# RFID.net
KiCad netlist of a schematic drawn in Altium Designer
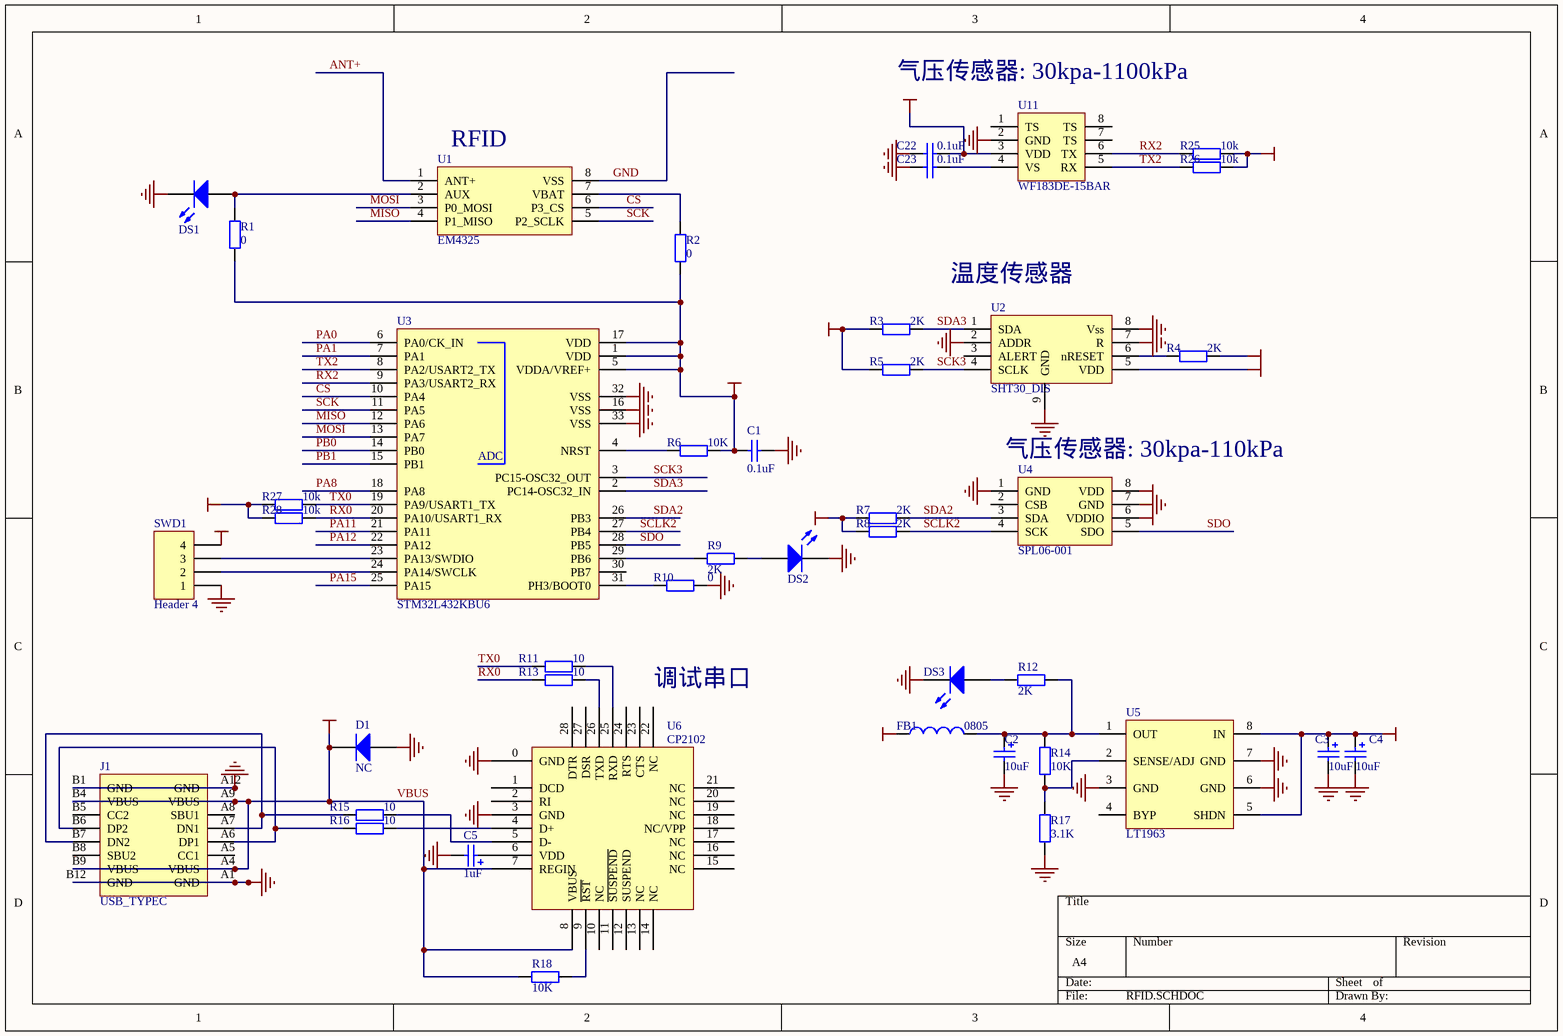
[diagram p0: RFID.SCHDOC]

(export (version "E")
  (design (tool "Eeschema 10.0.6"))
  (components
    (comp (ref "C1")
      (value "0.1uF")
      (footprint "0805")
      (description "Capacitor")
      (fields (field (name "PUBLISHER") "Altium Limited"))
      (libsource (lib "SCHALL") (part "Cap"))
    )
    (comp (ref "C2")
      (value "10uF")
      (footprint "1206")
      (description "Polarized Capacitor (Radial)")
      (fields (field (name "PUBLISHER") "Altium Limited"))
      (libsource (lib "SCHALL") (part "Cap Pol1"))
    )
    (comp (ref "C3")
      (value "10uF")
      (footprint "1206")
      (description "Polarized Capacitor (Radial)")
      (fields (field (name "PUBLISHER") "Altium Limited"))
      (libsource (lib "SCHALL") (part "Cap Pol1"))
    )
    (comp (ref "C4")
      (value "10uF")
      (footprint "1206")
      (description "Polarized Capacitor (Radial)")
      (fields (field (name "PUBLISHER") "Altium Limited"))
      (libsource (lib "SCHALL") (part "Cap Pol1"))
    )
    (comp (ref "C5")
      (value "1uF")
      (footprint "0805")
      (description "Polarized Capacitor (Radial)")
      (fields (field (name "PUBLISHER") "Altium Limited"))
      (libsource (lib "SCHALL") (part "Cap Pol1"))
    )
    (comp (ref "C22")
      (value "0.1uF")
      (footprint "0805")
      (description "Capacitor")
      (fields (field (name "PUBLISHER") "Altium Limited"))
      (libsource (lib "SCHALL") (part "Cap"))
    )
    (comp (ref "C23")
      (value "0.1uF")
      (footprint "0805")
      (description "Capacitor")
      (fields (field (name "PUBLISHER") "Altium Limited"))
      (libsource (lib "SCHALL") (part "Cap"))
    )
    (comp (ref "D1")
      (value "NC")
      (footprint "DFLS240L")
      (description "Default Diode")
      (fields (field (name "PUBLISHER") "Altium Limited"))
      (libsource (lib "SCHALL") (part "Diode"))
    )
    (comp (ref "DS1")
      (value "LED")
      (footprint "0603")
      (description "Typical BLUE SiC LED")
      (fields (field (name "PUBLISHER") "Altium Limited"))
      (libsource (lib "sch_lib") (part "LED"))
    )
    (comp (ref "DS2")
      (value "LED")
      (footprint "0603")
      (description "Typical BLUE SiC LED")
      (fields (field (name "PUBLISHER") "Altium Limited"))
      (libsource (lib "SCHALL") (part "LED"))
    )
    (comp (ref "DS3")
      (value "LED")
      (footprint "0603")
      (description "Typical BLUE SiC LED")
      (fields (field (name "PUBLISHER") "Altium Limited"))
      (libsource (lib "SCHALL") (part "LED"))
    )
    (comp (ref "FB1")
      (value "0805")
      (footprint "0805")
      (description "Inductor")
      (fields (field (name "PUBLISHER") "Altium Limited"))
      (libsource (lib "SCHALL") (part "Inductor"))
    )
    (comp (ref "J1")
      (value "USB_TYPEC")
      (footprint "USB_TYPEC_16")
      (libsource (lib "sch_lib") (part "USB_TYPEC"))
    )
    (comp (ref "R1")
      (value "0")
      (footprint "0603")
      (description "Resistor")
      (fields (field (name "PUBLISHER") "Altium Limited"))
      (libsource (lib "") (part "Res2_2"))
    )
    (comp (ref "R2")
      (value "0")
      (footprint "0603")
      (description "Resistor")
      (fields (field (name "PUBLISHER") "Altium Limited"))
      (libsource (lib "") (part "Res2_2"))
    )
    (comp (ref "R3")
      (value "2K")
      (footprint "0603")
      (description "Resistor")
      (fields (field (name "PUBLISHER") "Altium Limited"))
      (libsource (lib "SCHALL") (part "Res2"))
    )
    (comp (ref "R4")
      (value "2K")
      (footprint "0603")
      (description "Resistor")
      (fields (field (name "PUBLISHER") "Altium Limited"))
      (libsource (lib "SCHALL") (part "Res2"))
    )
    (comp (ref "R5")
      (value "2K")
      (footprint "0603")
      (description "Resistor")
      (fields (field (name "PUBLISHER") "Altium Limited"))
      (libsource (lib "SCHALL") (part "Res2"))
    )
    (comp (ref "R6")
      (value "10K")
      (footprint "0603")
      (description "Resistor")
      (fields (field (name "PUBLISHER") "Altium Limited"))
      (libsource (lib "") (part "Res2_1"))
    )
    (comp (ref "R7")
      (value "2K")
      (footprint "0603")
      (description "Resistor")
      (fields (field (name "PUBLISHER") "Altium Limited"))
      (libsource (lib "SCHALL") (part "Res2"))
    )
    (comp (ref "R8")
      (value "2K")
      (footprint "0603")
      (description "Resistor")
      (fields (field (name "PUBLISHER") "Altium Limited"))
      (libsource (lib "SCHALL") (part "Res2"))
    )
    (comp (ref "R9")
      (value "2K")
      (footprint "0603")
      (description "Resistor")
      (fields (field (name "PUBLISHER") "Altium Limited"))
      (libsource (lib "") (part "Res2_1"))
    )
    (comp (ref "R10")
      (value "0")
      (footprint "0603")
      (description "Resistor")
      (fields (field (name "PUBLISHER") "Altium Limited"))
      (libsource (lib "") (part "Res2_1"))
    )
    (comp (ref "R11")
      (value "10")
      (footprint "0603")
      (description "Resistor")
      (fields (field (name "PUBLISHER") "Altium Limited"))
      (libsource (lib "SCHALL") (part "Res2"))
    )
    (comp (ref "R12")
      (value "2K")
      (footprint "0603")
      (description "Resistor")
      (fields (field (name "PUBLISHER") "Altium Limited"))
      (libsource (lib "SCHALL") (part "Res2"))
    )
    (comp (ref "R13")
      (value "10")
      (footprint "0603")
      (description "Resistor")
      (fields (field (name "PUBLISHER") "Altium Limited"))
      (libsource (lib "SCHALL") (part "Res2"))
    )
    (comp (ref "R14")
      (value "10K")
      (footprint "0603")
      (description "Resistor")
      (fields (field (name "PUBLISHER") "Altium Limited"))
      (libsource (lib "") (part "Res2_2"))
    )
    (comp (ref "R15")
      (value "10")
      (footprint "0603")
      (description "Resistor")
      (fields (field (name "PUBLISHER") "Altium Limited"))
      (libsource (lib "SCHALL") (part "Res2"))
    )
    (comp (ref "R16")
      (value "10")
      (footprint "0603")
      (description "Resistor")
      (fields (field (name "PUBLISHER") "Altium Limited"))
      (libsource (lib "SCHALL") (part "Res2"))
    )
    (comp (ref "R17")
      (value "3.1K")
      (footprint "0603")
      (description "Resistor")
      (fields (field (name "PUBLISHER") "Altium Limited"))
      (libsource (lib "") (part "Res2_2"))
    )
    (comp (ref "R18")
      (value "10K")
      (footprint "0603")
      (description "Resistor")
      (fields (field (name "PUBLISHER") "Altium Limited"))
      (libsource (lib "SCHALL") (part "Res"))
    )
    (comp (ref "R25")
      (value "10k")
      (footprint "0603")
      (description "Resistor")
      (fields (field (name "PUBLISHER") "Altium Limited"))
      (libsource (lib "SCHALL") (part "Res2"))
    )
    (comp (ref "R26")
      (value "10k")
      (footprint "0603")
      (description "Resistor")
      (fields (field (name "PUBLISHER") "Altium Limited"))
      (libsource (lib "SCHALL") (part "Res2"))
    )
    (comp (ref "R27")
      (value "10k")
      (footprint "0603")
      (description "Resistor")
      (fields (field (name "PUBLISHER") "Altium Limited"))
      (libsource (lib "SCHALL") (part "Res2"))
    )
    (comp (ref "R28")
      (value "10k")
      (footprint "0603")
      (description "Resistor")
      (fields (field (name "PUBLISHER") "Altium Limited"))
      (libsource (lib "SCHALL") (part "Res2"))
    )
    (comp (ref "SWD1")
      (value "Header 4")
      (footprint "HDR1X4")
      (description "Header, 4-Pin")
      (fields (field (name "PUBLISHER") "Altium Limited"))
      (libsource (lib "sch_lib") (part "Header 4"))
    )
    (comp (ref "U1") (value "EM4325") (footprint "EM4325") (libsource (lib "sch_lib") (part "EM4325")))
    (comp (ref "U2") (value "SHT30_DIS") (footprint "SHT30") (libsource (lib "sch_lib") (part "SHT30")))
    (comp (ref "U3")
      (value "STM32L432KBU6")
      (footprint "STM32L432KBU6")
      (libsource (lib "sch_lib") (part "STM32L432KBU6"))
    )
    (comp (ref "U4")
      (value "SPL06-001")
      (footprint "SPL06-001")
      (libsource (lib "sch_lib") (part "SPL06-001"))
    )
    (comp (ref "U5") (value "LT1963") (footprint "AT24C64") (libsource (lib "SCHALL") (part "LT1763")))
    (comp (ref "U6") (value "CP2102") (footprint "CP2102") (libsource (lib "SCHALL") (part "CP2102")))
    (comp (ref "U11")
      (value "WF183DE-15BAR")
      (footprint "WF183D")
      (libsource (lib "sch_lib") (part "WF183D"))
    )
  )
  (nets
    (net (code "1") (name "/ANT+") (class "Default")
      (node (ref "U1") (pin "1") (pinfunction "ANT+_1") (pintype "passive"))
    )
    (net (code "2") (name "/CS") (class "Default")
      (node (ref "U1") (pin "6") (pinfunction "P3_CS_6") (pintype "passive"))
      (node (ref "U3") (pin "10") (pinfunction "PA4_10") (pintype "passive"))
    )
    (net (code "3") (name "/MISO") (class "Default")
      (node (ref "U1") (pin "4") (pinfunction "P1_MISO_4") (pintype "passive"))
      (node (ref "U3") (pin "12") (pinfunction "PA6_12") (pintype "passive"))
    )
    (net (code "4") (name "/MOSI") (class "Default")
      (node (ref "U1") (pin "3") (pinfunction "P0_MOSI_3") (pintype "passive"))
      (node (ref "U3") (pin "13") (pinfunction "PA7_13") (pintype "passive"))
    )
    (net (code "5") (name "/PA0") (class "Default")
      (node (ref "U3") (pin "6") (pinfunction "PA0/CK_IN_6") (pintype "passive"))
    )
    (net (code "6") (name "/PA1") (class "Default")
      (node (ref "U3") (pin "7") (pinfunction "PA1_7") (pintype "passive"))
    )
    (net (code "7") (name "/PA8") (class "Default")
      (node (ref "U3") (pin "18") (pinfunction "PA8_18") (pintype "passive"))
    )
    (net (code "8") (name "/PA11") (class "Default")
      (node (ref "U3") (pin "21") (pinfunction "PA11_21") (pintype "passive"))
    )
    (net (code "9") (name "/PA12") (class "Default")
      (node (ref "U3") (pin "22") (pinfunction "PA12_22") (pintype "passive"))
    )
    (net (code "10") (name "/PA15") (class "Default")
      (node (ref "U3") (pin "25") (pinfunction "PA15_25") (pintype "passive"))
    )
    (net (code "11") (name "/PB0") (class "Default")
      (node (ref "U3") (pin "14") (pinfunction "PB0_14") (pintype "passive"))
    )
    (net (code "12") (name "/PB1") (class "Default")
      (node (ref "U3") (pin "15") (pinfunction "PB1_15") (pintype "passive"))
    )
    (net (code "13") (name "/RX0") (class "Default")
      (node (ref "R13") (pin "1") (pinfunction "1_1") (pintype "passive"))
      (node (ref "R28") (pin "2") (pinfunction "2_2") (pintype "passive"))
      (node (ref "U3") (pin "20") (pinfunction "PA10/USART1_RX_20") (pintype "passive"))
    )
    (net (code "14") (name "/RX2") (class "Default")
      (node (ref "R25") (pin "1") (pinfunction "1_1") (pintype "passive"))
      (node (ref "U11") (pin "6") (pinfunction "TX_6") (pintype "passive"))
      (node (ref "U3") (pin "9") (pinfunction "PA3/USART2_RX_9") (pintype "passive"))
    )
    (net (code "15") (name "/SCK") (class "Default")
      (node (ref "U1") (pin "5") (pinfunction "P2_SCLK_5") (pintype "passive"))
      (node (ref "U3") (pin "11") (pinfunction "PA5_11") (pintype "passive"))
    )
    (net (code "16") (name "/SCK3") (class "Default")
      (node (ref "R5") (pin "2") (pinfunction "2_2") (pintype "passive"))
      (node (ref "U2") (pin "4") (pinfunction "SCLK_4") (pintype "passive"))
      (node (ref "U3") (pin "3") (pinfunction "PC15-OSC32_OUT_3") (pintype "passive"))
    )
    (net (code "17") (name "/SCLK2") (class "Default")
      (node (ref "R8") (pin "2") (pinfunction "2_2") (pintype "passive"))
      (node (ref "U3") (pin "27") (pinfunction "PB4_27") (pintype "passive"))
      (node (ref "U4") (pin "4") (pinfunction "SCK_4") (pintype "passive"))
    )
    (net (code "18") (name "/SDA2") (class "Default")
      (node (ref "R7") (pin "2") (pinfunction "2_2") (pintype "passive"))
      (node (ref "U3") (pin "26") (pinfunction "PB3_26") (pintype "passive"))
      (node (ref "U4") (pin "3") (pinfunction "SDA_3") (pintype "passive"))
    )
    (net (code "19") (name "/SDA3") (class "Default")
      (node (ref "R3") (pin "2") (pinfunction "2_2") (pintype "passive"))
      (node (ref "U2") (pin "1") (pinfunction "SDA_1") (pintype "passive"))
      (node (ref "U3") (pin "2") (pinfunction "PC14-OSC32_IN_2") (pintype "passive"))
    )
    (net (code "20") (name "/SDO") (class "Default")
      (node (ref "U3") (pin "28") (pinfunction "PB5_28") (pintype "passive"))
      (node (ref "U4") (pin "5") (pinfunction "SDO_5") (pintype "passive"))
    )
    (net (code "21") (name "/TX0") (class "Default")
      (node (ref "R11") (pin "1") (pinfunction "1_1") (pintype "passive"))
      (node (ref "R27") (pin "2") (pinfunction "2_2") (pintype "passive"))
      (node (ref "U3") (pin "19") (pinfunction "PA9/USART1_TX_19") (pintype "passive"))
    )
    (net (code "22") (name "/TX2") (class "Default")
      (node (ref "R26") (pin "1") (pinfunction "1_1") (pintype "passive"))
      (node (ref "U11") (pin "5") (pinfunction "RX_5") (pintype "passive"))
      (node (ref "U3") (pin "8") (pinfunction "PA2/USART2_TX_8") (pintype "passive"))
    )
    (net (code "23") (name "GND") (class "Default")
      (node (ref "C1") (pin "1") (pinfunction "1_1") (pintype "passive"))
      (node (ref "C2") (pin "2") (pinfunction "2_2") (pintype "passive"))
      (node (ref "C22") (pin "1") (pinfunction "1_1") (pintype "passive"))
      (node (ref "C23") (pin "1") (pinfunction "1_1") (pintype "passive"))
      (node (ref "C3") (pin "2") (pinfunction "2_2") (pintype "passive"))
      (node (ref "C4") (pin "2") (pinfunction "2_2") (pintype "passive"))
      (node (ref "C5") (pin "2") (pinfunction "2_2") (pintype "passive"))
      (node (ref "D1") (pin "1") (pinfunction "A_1") (pintype "passive"))
      (node (ref "DS1") (pin "2") (pinfunction "K_2") (pintype "passive"))
      (node (ref "DS2") (pin "2") (pinfunction "K_2") (pintype "passive"))
      (node (ref "DS3") (pin "2") (pinfunction "K_2") (pintype "passive"))
      (node (ref "J1") (pin "A1") (pinfunction "GND_A1") (pintype "passive"))
      (node (ref "J1") (pin "A12") (pinfunction "GND_A12") (pintype "passive"))
      (node (ref "J1") (pin "B1") (pinfunction "GND_B1") (pintype "passive"))
      (node (ref "J1") (pin "B12") (pinfunction "GND_B12") (pintype "passive"))
      (node (ref "R10") (pin "1") (pinfunction "1_1") (pintype "passive"))
      (node (ref "R17") (pin "1") (pinfunction "1_1") (pintype "passive"))
      (node (ref "SWD1") (pin "1") (pinfunction "1_1") (pintype "passive"))
      (node (ref "U1") (pin "8") (pinfunction "VSS_8") (pintype "passive"))
      (node (ref "U11") (pin "2") (pinfunction "GND_2") (pintype "passive"))
      (node (ref "U2") (pin "2") (pinfunction "ADDR_2") (pintype "passive"))
      (node (ref "U2") (pin "7") (pinfunction "R_7") (pintype "passive"))
      (node (ref "U2") (pin "8") (pinfunction "Vss_8") (pintype "passive"))
      (node (ref "U2") (pin "9") (pinfunction "GND_9") (pintype "passive"))
      (node (ref "U3") (pin "16") (pinfunction "VSS_16") (pintype "passive"))
      (node (ref "U3") (pin "32") (pinfunction "VSS_32") (pintype "passive"))
      (node (ref "U3") (pin "33") (pinfunction "VSS_33") (pintype "passive"))
      (node (ref "U4") (pin "1") (pinfunction "GND_1") (pintype "passive"))
      (node (ref "U4") (pin "7") (pinfunction "GND_7") (pintype "passive"))
      (node (ref "U5") (pin "3") (pinfunction "GND_3") (pintype "passive"))
      (node (ref "U5") (pin "6") (pinfunction "GND_6") (pintype "passive"))
      (node (ref "U5") (pin "7") (pinfunction "GND_7") (pintype "passive"))
      (node (ref "U6") (pin "0") (pinfunction "GND_0") (pintype "passive"))
      (node (ref "U6") (pin "3") (pinfunction "GND_3") (pintype "passive"))
    )
    (net (code "24") (name "Net-(DS1-A)") (class "Default")
      (node (ref "DS1") (pin "1") (pinfunction "A_1") (pintype "passive"))
      (node (ref "R1") (pin "2") (pinfunction "2_2") (pintype "passive"))
      (node (ref "U1") (pin "2") (pinfunction "AUX_2") (pintype "passive"))
    )
    (net (code "25") (name "Net-(DS2-A)") (class "Default")
      (node (ref "DS2") (pin "1") (pinfunction "A_1") (pintype "passive"))
      (node (ref "R9") (pin "1") (pinfunction "1_1") (pintype "passive"))
    )
    (net (code "26") (name "Net-(DS3-A)") (class "Default")
      (node (ref "DS3") (pin "1") (pinfunction "A_1") (pintype "passive"))
      (node (ref "R12") (pin "1") (pinfunction "1_1") (pintype "passive"))
    )
    (net (code "27") (name "Net-(J1-DN1)") (class "Default")
      (node (ref "J1") (pin "A7") (pinfunction "DN1_A7") (pintype "passive"))
      (node (ref "J1") (pin "B7") (pinfunction "DN2_B7") (pintype "passive"))
      (node (ref "R15") (pin "1") (pinfunction "1_1") (pintype "passive"))
    )
    (net (code "28") (name "Net-(J1-DP1)") (class "Default")
      (node (ref "J1") (pin "A6") (pinfunction "DP1_A6") (pintype "passive"))
      (node (ref "J1") (pin "B6") (pinfunction "DP2_B6") (pintype "passive"))
      (node (ref "R16") (pin "1") (pinfunction "1_1") (pintype "passive"))
    )
    (net (code "29") (name "Net-(U1-VBAT)") (class "Default")
      (node (ref "R2") (pin "2") (pinfunction "2_2") (pintype "passive"))
      (node (ref "U1") (pin "7") (pinfunction "VBAT_7") (pintype "passive"))
    )
    (net (code "30") (name "Net-(U2-nRESET)") (class "Default")
      (node (ref "R4") (pin "1") (pinfunction "1_1") (pintype "passive"))
      (node (ref "U2") (pin "6") (pinfunction "nRESET_6") (pintype "passive"))
    )
    (net (code "31") (name "Net-(U3-NRST)") (class "Default")
      (node (ref "R6") (pin "2") (pinfunction "2_2") (pintype "passive"))
      (node (ref "U3") (pin "4") (pinfunction "NRST_4") (pintype "passive"))
    )
    (net (code "32") (name "Net-(U3-PA13{slash}SWDIO)") (class "Default")
      (node (ref "SWD1") (pin "3") (pinfunction "3_3") (pintype "passive"))
      (node (ref "U3") (pin "23") (pinfunction "PA13/SWDIO_23") (pintype "passive"))
    )
    (net (code "33") (name "Net-(U3-PA14{slash}SWCLK)") (class "Default")
      (node (ref "SWD1") (pin "2") (pinfunction "2_2") (pintype "passive"))
      (node (ref "U3") (pin "24") (pinfunction "PA14/SWCLK_24") (pintype "passive"))
    )
    (net (code "34") (name "Net-(U3-PB6)") (class "Default")
      (node (ref "R9") (pin "2") (pinfunction "2_2") (pintype "passive"))
      (node (ref "U3") (pin "29") (pinfunction "PB6_29") (pintype "passive"))
    )
    (net (code "35") (name "Net-(U3-PH3{slash}BOOT0)") (class "Default")
      (node (ref "R10") (pin "2") (pinfunction "2_2") (pintype "passive"))
      (node (ref "U3") (pin "31") (pinfunction "PH3/BOOT0_31") (pintype "passive"))
    )
    (net (code "36") (name "Net-(U5-OUT)") (class "Default")
      (node (ref "C2") (pin "1") (pinfunction "1_1") (pintype "passive"))
      (node (ref "FB1") (pin "2") (pinfunction "2_2") (pintype "passive"))
      (node (ref "R12") (pin "2") (pinfunction "2_2") (pintype "passive"))
      (node (ref "R14") (pin "2") (pinfunction "2_2") (pintype "passive"))
      (node (ref "U5") (pin "1") (pinfunction "OUT_1") (pintype "passive"))
    )
    (net (code "37") (name "Net-(U5-SENSE{slash}ADJ)") (class "Default")
      (node (ref "R14") (pin "1") (pinfunction "1_1") (pintype "passive"))
      (node (ref "R17") (pin "2") (pinfunction "2_2") (pintype "passive"))
      (node (ref "U5") (pin "2") (pinfunction "SENSE/ADJ_2") (pintype "passive"))
    )
    (net (code "38") (name "Net-(U6-D+)") (class "Default")
      (node (ref "R16") (pin "2") (pinfunction "2_2") (pintype "passive"))
      (node (ref "U6") (pin "4") (pinfunction "D+_4") (pintype "passive"))
    )
    (net (code "39") (name "Net-(U6-D-)") (class "Default")
      (node (ref "R15") (pin "2") (pinfunction "2_2") (pintype "passive"))
      (node (ref "U6") (pin "5") (pinfunction "D-_5") (pintype "passive"))
    )
    (net (code "40") (name "Net-(U6-RXD)") (class "Default")
      (node (ref "R11") (pin "2") (pinfunction "2_2") (pintype "passive"))
      (node (ref "U6") (pin "25") (pinfunction "RXD_25") (pintype "passive"))
    )
    (net (code "41") (name "Net-(U6-TXD)") (class "Default")
      (node (ref "R13") (pin "2") (pinfunction "2_2") (pintype "passive"))
      (node (ref "U6") (pin "26") (pinfunction "TXD_26") (pintype "passive"))
    )
    (net (code "42") (name "Net-(U6-VDD)") (class "Default")
      (node (ref "C5") (pin "1") (pinfunction "1_1") (pintype "passive"))
      (node (ref "U6") (pin "6") (pinfunction "VDD_6") (pintype "passive"))
    )
    (net (code "43") (name "Net-(U6-~{RST})") (class "Default")
      (node (ref "R18") (pin "2") (pinfunction "2_2") (pintype "passive"))
      (node (ref "U6") (pin "9") (pinfunction "~{RST}_9") (pintype "passive"))
    )
    (net (code "44") (name "Net-(U11-VS)") (class "Default")
      (node (ref "C23") (pin "2") (pinfunction "2_2") (pintype "passive"))
      (node (ref "U11") (pin "4") (pinfunction "VS_4") (pintype "passive"))
    )
    (net (code "45") (name "VCC3V3") (class "Default")
      (node (ref "C1") (pin "2") (pinfunction "2_2") (pintype "passive"))
      (node (ref "C22") (pin "2") (pinfunction "2_2") (pintype "passive"))
      (node (ref "FB1") (pin "1") (pinfunction "1_1") (pintype "passive"))
      (node (ref "R1") (pin "1") (pinfunction "1_1") (pintype "passive"))
      (node (ref "R2") (pin "1") (pinfunction "1_1") (pintype "passive"))
      (node (ref "R25") (pin "2") (pinfunction "2_2") (pintype "passive"))
      (node (ref "R26") (pin "2") (pinfunction "2_2") (pintype "passive"))
      (node (ref "R27") (pin "1") (pinfunction "1_1") (pintype "passive"))
      (node (ref "R28") (pin "1") (pinfunction "1_1") (pintype "passive"))
      (node (ref "R3") (pin "1") (pinfunction "1_1") (pintype "passive"))
      (node (ref "R4") (pin "2") (pinfunction "2_2") (pintype "passive"))
      (node (ref "R5") (pin "1") (pinfunction "1_1") (pintype "passive"))
      (node (ref "R6") (pin "1") (pinfunction "1_1") (pintype "passive"))
      (node (ref "R7") (pin "1") (pinfunction "1_1") (pintype "passive"))
      (node (ref "R8") (pin "1") (pinfunction "1_1") (pintype "passive"))
      (node (ref "SWD1") (pin "4") (pinfunction "4_4") (pintype "passive"))
      (node (ref "U11") (pin "3") (pinfunction "VDD_3") (pintype "passive"))
      (node (ref "U2") (pin "5") (pinfunction "VDD_5") (pintype "passive"))
      (node (ref "U3") (pin "1") (pinfunction "VDD_1") (pintype "passive"))
      (node (ref "U3") (pin "17") (pinfunction "VDD_17") (pintype "passive"))
      (node (ref "U3") (pin "5") (pinfunction "VDDA/VREF+_5") (pintype "passive"))
      (node (ref "U4") (pin "6") (pinfunction "VDDIO_6") (pintype "passive"))
      (node (ref "U4") (pin "8") (pinfunction "VDD_8") (pintype "passive"))
    )
    (net (code "46") (name "VCC_5V0") (class "Default")
      (node (ref "C3") (pin "1") (pinfunction "1_1") (pintype "passive"))
      (node (ref "C4") (pin "1") (pinfunction "1_1") (pintype "passive"))
      (node (ref "D1") (pin "2") (pinfunction "K_2") (pintype "passive"))
      (node (ref "J1") (pin "A4") (pinfunction "VBUS_A4") (pintype "passive"))
      (node (ref "J1") (pin "A9") (pinfunction "VBUS_A9") (pintype "passive"))
      (node (ref "J1") (pin "B4") (pinfunction "VBUS_B4") (pintype "passive"))
      (node (ref "J1") (pin "B9") (pinfunction "VBUS_B9") (pintype "passive"))
      (node (ref "R18") (pin "1") (pinfunction "1_1") (pintype "passive"))
      (node (ref "U5") (pin "5") (pinfunction "SHDN_5") (pintype "passive"))
      (node (ref "U5") (pin "8") (pinfunction "IN_8") (pintype "passive"))
      (node (ref "U6") (pin "7") (pinfunction "REGIN_7") (pintype "passive"))
      (node (ref "U6") (pin "8") (pinfunction "VBUS_8") (pintype "passive"))
    )
    (net (code "47") (name "unconnected-(J1-CC1-PadA5)") (class "Default")
      (node (ref "J1") (pin "A5") (pinfunction "CC1_A5") (pintype "passive"))
    )
    (net (code "48") (name "unconnected-(J1-CC2-PadB5)") (class "Default")
      (node (ref "J1") (pin "B5") (pinfunction "CC2_B5") (pintype "passive"))
    )
    (net (code "49") (name "unconnected-(J1-SBU1-PadA8)") (class "Default")
      (node (ref "J1") (pin "A8") (pinfunction "SBU1_A8") (pintype "passive"))
    )
    (net (code "50") (name "unconnected-(J1-SBU2-PadB8)") (class "Default")
      (node (ref "J1") (pin "B8") (pinfunction "SBU2_B8") (pintype "passive"))
    )
    (net (code "51") (name "unconnected-(U2-ALERT-Pad3)") (class "Default")
      (node (ref "U2") (pin "3") (pinfunction "ALERT_3") (pintype "passive"))
    )
    (net (code "52") (name "unconnected-(U3-PB7-Pad30)") (class "Default")
      (node (ref "U3") (pin "30") (pinfunction "PB7_30") (pintype "passive"))
    )
    (net (code "53") (name "unconnected-(U4-CSB-Pad2)") (class "Default")
      (node (ref "U4") (pin "2") (pinfunction "CSB_2") (pintype "passive"))
    )
    (net (code "54") (name "unconnected-(U5-BYP-Pad4)") (class "Default")
      (node (ref "U5") (pin "4") (pinfunction "BYP_4") (pintype "passive"))
    )
    (net (code "55") (name "unconnected-(U6-CTS-Pad23)") (class "Default")
      (node (ref "U6") (pin "23") (pinfunction "CTS_23") (pintype "passive"))
    )
    (net (code "56") (name "unconnected-(U6-DCD-Pad1)") (class "Default")
      (node (ref "U6") (pin "1") (pinfunction "DCD_1") (pintype "passive"))
    )
    (net (code "57") (name "unconnected-(U6-DSR-Pad27)") (class "Default")
      (node (ref "U6") (pin "27") (pinfunction "DSR_27") (pintype "passive"))
    )
    (net (code "58") (name "unconnected-(U6-DTR-Pad28)") (class "Default")
      (node (ref "U6") (pin "28") (pinfunction "DTR_28") (pintype "passive"))
    )
    (net (code "59") (name "unconnected-(U6-NC-Pad10)") (class "Default")
      (node (ref "U6") (pin "10") (pinfunction "NC_10") (pintype "passive"))
    )
    (net (code "60") (name "unconnected-(U6-NC-Pad13)") (class "Default")
      (node (ref "U6") (pin "13") (pinfunction "NC_13") (pintype "passive"))
    )
    (net (code "61") (name "unconnected-(U6-NC-Pad14)") (class "Default")
      (node (ref "U6") (pin "14") (pinfunction "NC_14") (pintype "passive"))
    )
    (net (code "62") (name "unconnected-(U6-NC-Pad15)") (class "Default")
      (node (ref "U6") (pin "15") (pinfunction "NC_15") (pintype "passive"))
    )
    (net (code "63") (name "unconnected-(U6-NC-Pad16)") (class "Default")
      (node (ref "U6") (pin "16") (pinfunction "NC_16") (pintype "passive"))
    )
    (net (code "64") (name "unconnected-(U6-NC-Pad17)") (class "Default")
      (node (ref "U6") (pin "17") (pinfunction "NC_17") (pintype "passive"))
    )
    (net (code "65") (name "unconnected-(U6-NC-Pad19)") (class "Default")
      (node (ref "U6") (pin "19") (pinfunction "NC_19") (pintype "passive"))
    )
    (net (code "66") (name "unconnected-(U6-NC-Pad20)") (class "Default")
      (node (ref "U6") (pin "20") (pinfunction "NC_20") (pintype "passive"))
    )
    (net (code "67") (name "unconnected-(U6-NC-Pad21)") (class "Default")
      (node (ref "U6") (pin "21") (pinfunction "NC_21") (pintype "passive"))
    )
    (net (code "68") (name "unconnected-(U6-NC-Pad22)") (class "Default")
      (node (ref "U6") (pin "22") (pinfunction "NC_22") (pintype "passive"))
    )
    (net (code "69") (name "unconnected-(U6-NC{slash}VPP-Pad18)") (class "Default")
      (node (ref "U6") (pin "18") (pinfunction "NC/VPP_18") (pintype "passive"))
    )
    (net (code "70") (name "unconnected-(U6-RI-Pad2)") (class "Default")
      (node (ref "U6") (pin "2") (pinfunction "RI_2") (pintype "passive"))
    )
    (net (code "71") (name "unconnected-(U6-RTS-Pad24)") (class "Default")
      (node (ref "U6") (pin "24") (pinfunction "RTS_24") (pintype "passive"))
    )
    (net (code "72") (name "unconnected-(U6-SUSPEND-Pad12)") (class "Default")
      (node (ref "U6") (pin "12") (pinfunction "SUSPEND_12") (pintype "passive"))
    )
    (net (code "73") (name "unconnected-(U6-~{SUSPEND}-Pad11)") (class "Default")
      (node (ref "U6") (pin "11") (pinfunction "~{SUSPEND}_11") (pintype "passive"))
    )
    (net (code "74") (name "unconnected-(U11-TS-Pad1)") (class "Default")
      (node (ref "U11") (pin "1") (pinfunction "TS_1") (pintype "passive"))
    )
    (net (code "75") (name "unconnected-(U11-TS-Pad7)") (class "Default")
      (node (ref "U11") (pin "7") (pinfunction "TS_7") (pintype "passive"))
    )
    (net (code "76") (name "unconnected-(U11-TS-Pad8)") (class "Default")
      (node (ref "U11") (pin "8") (pinfunction "TS_8") (pintype "passive"))
    )
  )
)
